# SubLowVoltagePS.net
KiCad netlist of a schematic drawn in Altium Designer
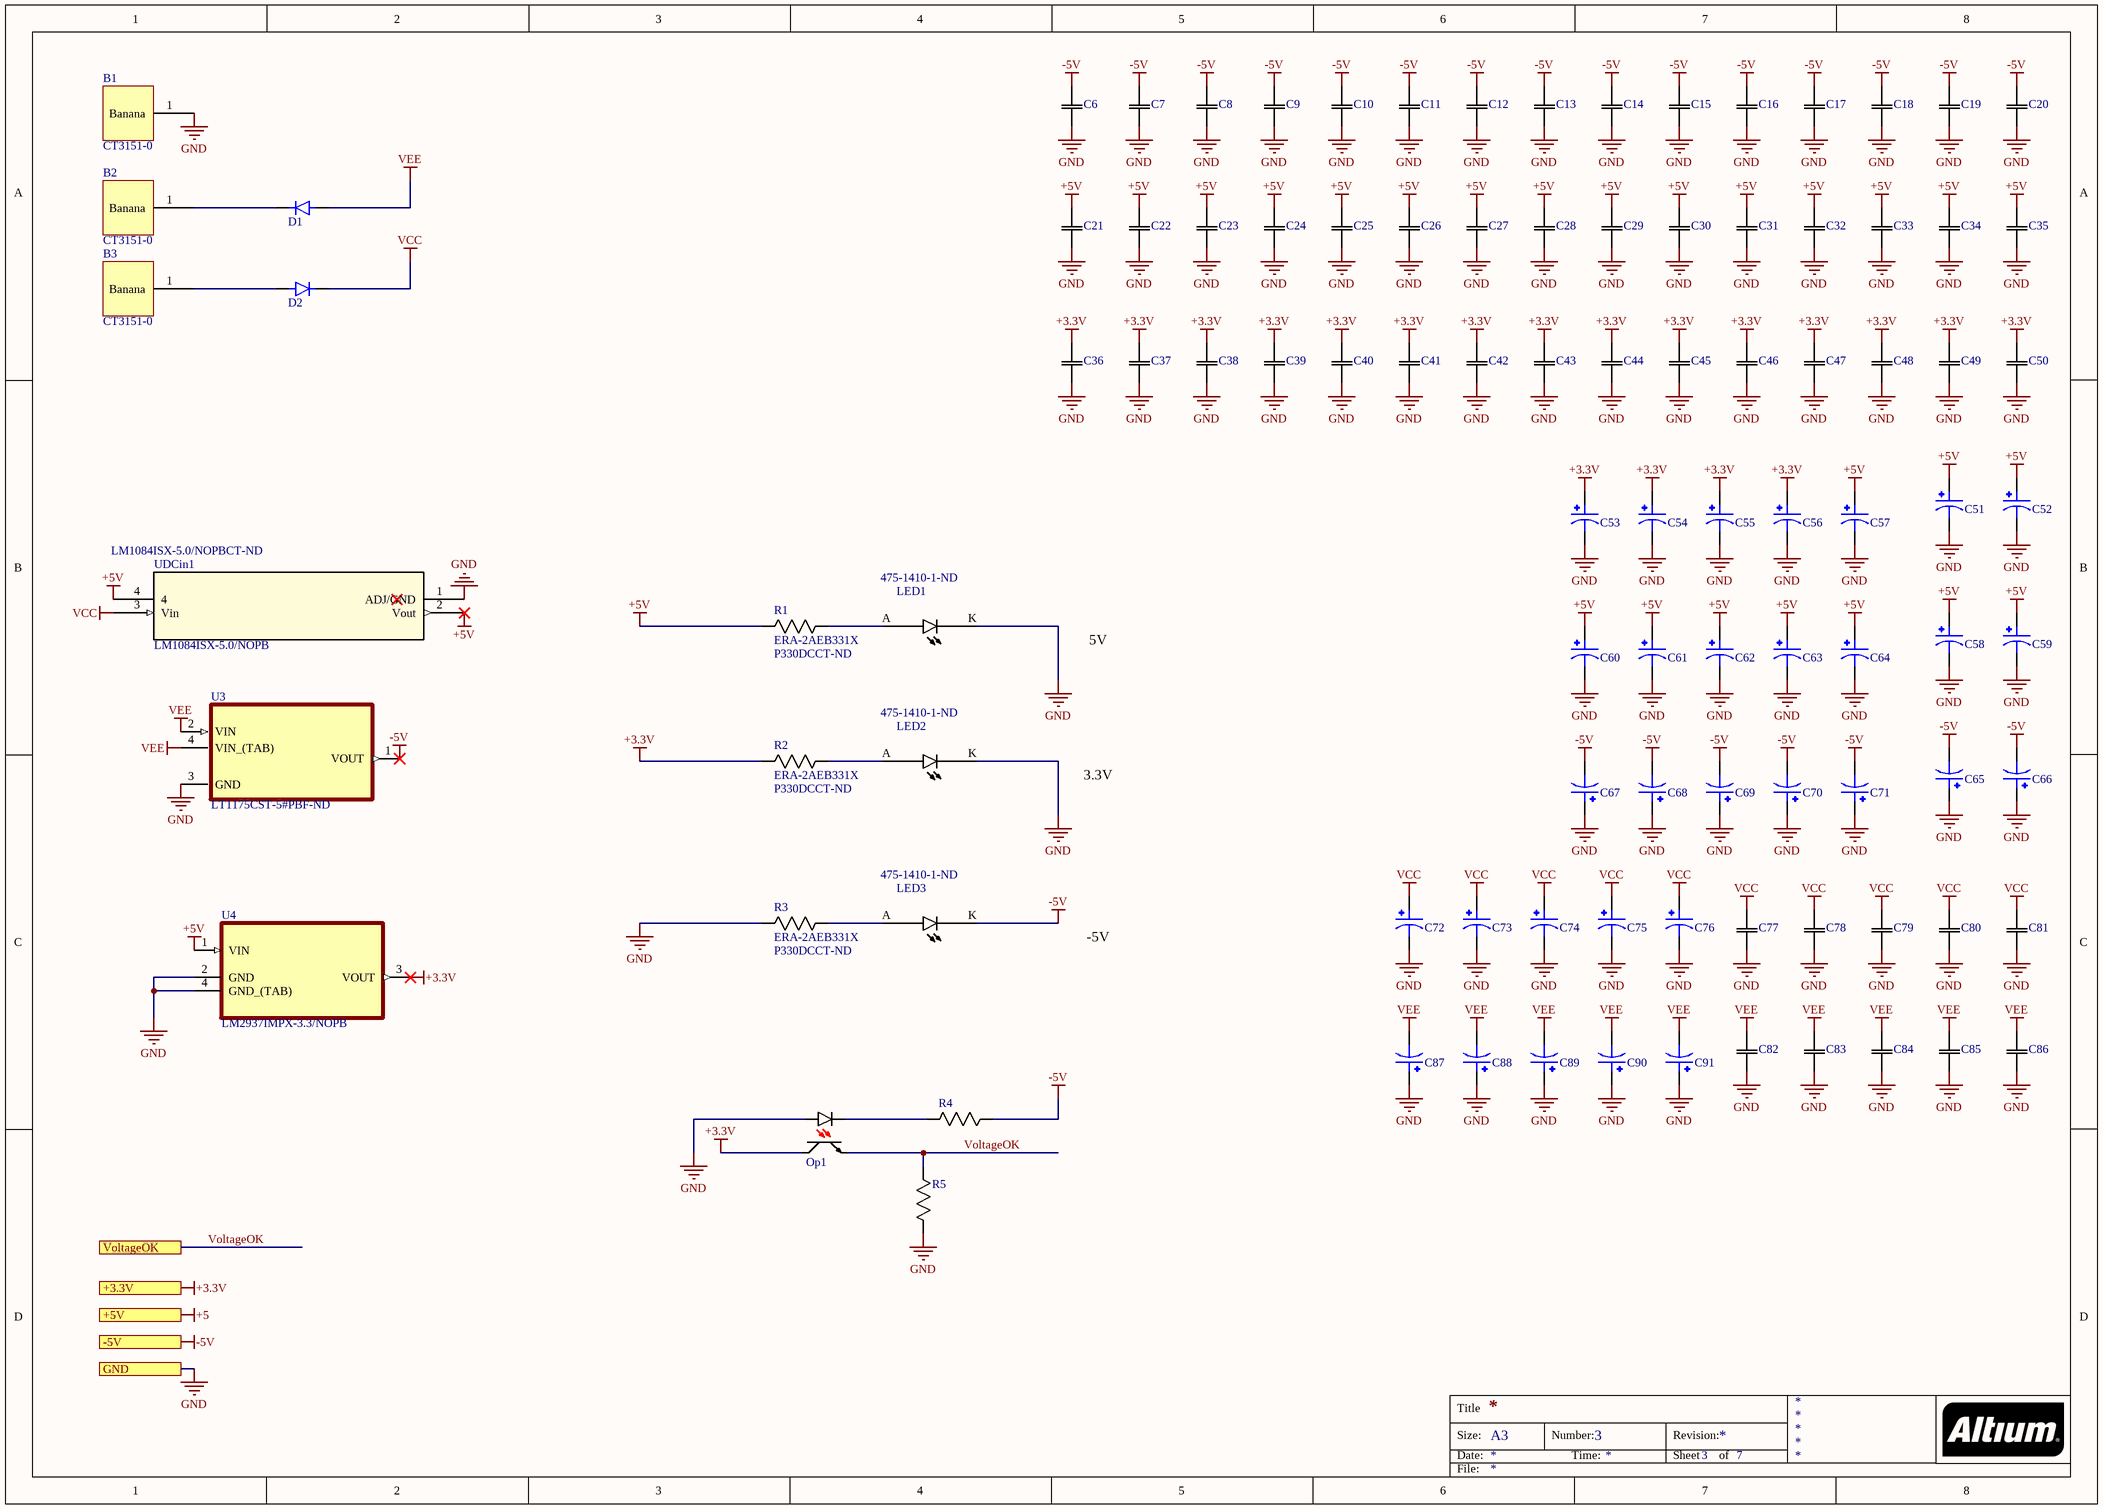
[diagram p0: SubLowVoltagePS.SchDoc]

(export (version "E")
  (design (tool "Eeschema 10.0.6"))
  (components
    (comp (ref "B1")
      (value "CT3151-0")
      (footprint "CT3151L")
      (libsource (lib "Afshin Library") (part "CT3151-0"))
    )
    (comp (ref "B2")
      (value "CT3151-0")
      (footprint "CT3151L")
      (libsource (lib "Afshin Library") (part "CT3151-0"))
    )
    (comp (ref "B3")
      (value "CT3151-0")
      (footprint "CT3151L")
      (libsource (lib "Afshin Library") (part "CT3151-0"))
    )
    (comp (ref "C6")
      (value "GRM155R71H102KA01J")
      (footprint "C0402")
      (libsource (lib "Afshin Library") (part "Cap_0402"))
    )
    (comp (ref "C7")
      (value "GRM155R71H102KA01J")
      (footprint "C0402")
      (libsource (lib "Afshin Library") (part "Cap_0402"))
    )
    (comp (ref "C8")
      (value "GRM155R71H102KA01J")
      (footprint "C0402")
      (libsource (lib "Afshin Library") (part "Cap_0402"))
    )
    (comp (ref "C9")
      (value "GRM155R71H102KA01J")
      (footprint "C0402")
      (libsource (lib "Afshin Library") (part "Cap_0402"))
    )
    (comp (ref "C10")
      (value "GRM155R71H102KA01J")
      (footprint "C0402")
      (libsource (lib "Afshin Library") (part "Cap_0402"))
    )
    (comp (ref "C11")
      (value "GRM155R71C103MA01D")
      (footprint "C0402")
      (libsource (lib "Afshin Library") (part "Cap_0402"))
    )
    (comp (ref "C12")
      (value "GRM155R71C103MA01D")
      (footprint "C0402")
      (libsource (lib "Afshin Library") (part "Cap_0402"))
    )
    (comp (ref "C13")
      (value "GRM155R71C103MA01D")
      (footprint "C0402")
      (libsource (lib "Afshin Library") (part "Cap_0402"))
    )
    (comp (ref "C14")
      (value "GRM155R71C103MA01D")
      (footprint "C0402")
      (libsource (lib "Afshin Library") (part "Cap_0402"))
    )
    (comp (ref "C15")
      (value "GRM155R71C103MA01D")
      (footprint "C0402")
      (libsource (lib "Afshin Library") (part "Cap_0402"))
    )
    (comp (ref "C16")
      (value "C0805C104Z5VACTU")
      (footprint "C0805")
      (libsource (lib "Afshin Library") (part "Cap_0805"))
    )
    (comp (ref "C17")
      (value "C0805C104Z5VACTU")
      (footprint "C0805")
      (libsource (lib "Afshin Library") (part "Cap_0805"))
    )
    (comp (ref "C18")
      (value "C0805C104Z5VACTU")
      (footprint "C0805")
      (libsource (lib "Afshin Library") (part "Cap_0805"))
    )
    (comp (ref "C19")
      (value "C0805C104Z5VACTU")
      (footprint "C0805")
      (libsource (lib "Afshin Library") (part "Cap_0805"))
    )
    (comp (ref "C20")
      (value "C0805C104Z5VACTU")
      (footprint "C0805")
      (libsource (lib "Afshin Library") (part "Cap_0805"))
    )
    (comp (ref "C21")
      (value "GRM155R71H102KA01J")
      (footprint "C0402")
      (libsource (lib "Afshin Library") (part "Cap_0402"))
    )
    (comp (ref "C22")
      (value "GRM155R71H102KA01J")
      (footprint "C0402")
      (libsource (lib "Afshin Library") (part "Cap_0402"))
    )
    (comp (ref "C23")
      (value "GRM155R71H102KA01J")
      (footprint "C0402")
      (libsource (lib "Afshin Library") (part "Cap_0402"))
    )
    (comp (ref "C24")
      (value "GRM155R71H102KA01J")
      (footprint "C0402")
      (libsource (lib "Afshin Library") (part "Cap_0402"))
    )
    (comp (ref "C25")
      (value "GRM155R71H102KA01J")
      (footprint "C0402")
      (libsource (lib "Afshin Library") (part "Cap_0402"))
    )
    (comp (ref "C26")
      (value "GRM155R71C103MA01D")
      (footprint "C0402")
      (libsource (lib "Afshin Library") (part "Cap_0402"))
    )
    (comp (ref "C27")
      (value "GRM155R71C103MA01D")
      (footprint "C0402")
      (libsource (lib "Afshin Library") (part "Cap_0402"))
    )
    (comp (ref "C28")
      (value "GRM155R71C103MA01D")
      (footprint "C0402")
      (libsource (lib "Afshin Library") (part "Cap_0402"))
    )
    (comp (ref "C29")
      (value "GRM155R71C103MA01D")
      (footprint "C0402")
      (libsource (lib "Afshin Library") (part "Cap_0402"))
    )
    (comp (ref "C30")
      (value "GRM155R71C103MA01D")
      (footprint "C0402")
      (libsource (lib "Afshin Library") (part "Cap_0402"))
    )
    (comp (ref "C31")
      (value "C0805C104Z5VACTU")
      (footprint "C0805")
      (libsource (lib "Afshin Library") (part "Cap_0805"))
    )
    (comp (ref "C32")
      (value "C0805C104Z5VACTU")
      (footprint "C0805")
      (libsource (lib "Afshin Library") (part "Cap_0805"))
    )
    (comp (ref "C33")
      (value "C0805C104Z5VACTU")
      (footprint "C0805")
      (libsource (lib "Afshin Library") (part "Cap_0805"))
    )
    (comp (ref "C34")
      (value "C0805C104Z5VACTU")
      (footprint "C0805")
      (libsource (lib "Afshin Library") (part "Cap_0805"))
    )
    (comp (ref "C35")
      (value "C0805C104Z5VACTU")
      (footprint "C0805")
      (libsource (lib "Afshin Library") (part "Cap_0805"))
    )
    (comp (ref "C36")
      (value "GRM155R71H102KA01J")
      (footprint "C0402")
      (libsource (lib "Afshin Library") (part "Cap_0402"))
    )
    (comp (ref "C37")
      (value "GRM155R71H102KA01J")
      (footprint "C0402")
      (libsource (lib "Afshin Library") (part "Cap_0402"))
    )
    (comp (ref "C38")
      (value "GRM155R71H102KA01J")
      (footprint "C0402")
      (libsource (lib "Afshin Library") (part "Cap_0402"))
    )
    (comp (ref "C39")
      (value "GRM155R71H102KA01J")
      (footprint "C0402")
      (libsource (lib "Afshin Library") (part "Cap_0402"))
    )
    (comp (ref "C40")
      (value "GRM155R71H102KA01J")
      (footprint "C0402")
      (libsource (lib "Afshin Library") (part "Cap_0402"))
    )
    (comp (ref "C41")
      (value "GRM155R71C103MA01D")
      (footprint "C0402")
      (libsource (lib "Afshin Library") (part "Cap_0402"))
    )
    (comp (ref "C42")
      (value "GRM155R71C103MA01D")
      (footprint "C0402")
      (libsource (lib "Afshin Library") (part "Cap_0402"))
    )
    (comp (ref "C43")
      (value "GRM155R71C103MA01D")
      (footprint "C0402")
      (libsource (lib "Afshin Library") (part "Cap_0402"))
    )
    (comp (ref "C44")
      (value "GRM155R71C103MA01D")
      (footprint "C0402")
      (libsource (lib "Afshin Library") (part "Cap_0402"))
    )
    (comp (ref "C45")
      (value "GRM155R71C103MA01D")
      (footprint "C0402")
      (libsource (lib "Afshin Library") (part "Cap_0402"))
    )
    (comp (ref "C46")
      (value "C0805C104Z5VACTU")
      (footprint "C0805")
      (libsource (lib "Afshin Library") (part "Cap_0805"))
    )
    (comp (ref "C47")
      (value "C0805C104Z5VACTU")
      (footprint "C0805")
      (libsource (lib "Afshin Library") (part "Cap_0805"))
    )
    (comp (ref "C48")
      (value "C0805C104Z5VACTU")
      (footprint "C0805")
      (libsource (lib "Afshin Library") (part "Cap_0805"))
    )
    (comp (ref "C49")
      (value "C0805C104Z5VACTU")
      (footprint "C0805")
      (libsource (lib "Afshin Library") (part "Cap_0805"))
    )
    (comp (ref "C50")
      (value "C0805C104Z5VACTU")
      (footprint "C0805")
      (libsource (lib "Afshin Library") (part "Cap_0805"))
    )
    (comp (ref "C51")
      (value "T55A107M6R3C0200")
      (footprint "C1206")
      (description "Tantalium")
      (libsource (lib "") (part "Cap_1206_1"))
    )
    (comp (ref "C52")
      (value "T55A107M6R3C0200")
      (footprint "C1206")
      (description "Tantalium")
      (libsource (lib "") (part "Cap_1206_1"))
    )
    (comp (ref "C53")
      (value "T491A104K050AT")
      (footprint "C1206")
      (description "Tantalium")
      (libsource (lib "") (part "Cap_1206_1"))
    )
    (comp (ref "C54")
      (value "T491A104K050AT")
      (footprint "C1206")
      (description "Tantalium")
      (libsource (lib "") (part "Cap_1206_1"))
    )
    (comp (ref "C55")
      (value "T491A104K050AT")
      (footprint "C1206")
      (description "Tantalium")
      (libsource (lib "") (part "Cap_1206_1"))
    )
    (comp (ref "C56")
      (value "T491A104K050AT")
      (footprint "C1206")
      (description "Tantalium")
      (libsource (lib "") (part "Cap_1206_1"))
    )
    (comp (ref "C57")
      (value "T491A104K050AT")
      (footprint "C1206")
      (description "Tantalium")
      (libsource (lib "") (part "Cap_1206_1"))
    )
    (comp (ref "C58")
      (value "T55A107M6R3C0200")
      (footprint "C1206")
      (description "Tantalium")
      (libsource (lib "") (part "Cap_1206_1"))
    )
    (comp (ref "C59")
      (value "T55A107M6R3C0200")
      (footprint "C1206")
      (description "Tantalium")
      (libsource (lib "") (part "Cap_1206_1"))
    )
    (comp (ref "C60")
      (value "T491A104K050AT")
      (footprint "C1206")
      (description "Tantalium")
      (libsource (lib "") (part "Cap_1206_1"))
    )
    (comp (ref "C61")
      (value "T491A104K050AT")
      (footprint "C1206")
      (description "Tantalium")
      (libsource (lib "") (part "Cap_1206_1"))
    )
    (comp (ref "C62")
      (value "T491A104K050AT")
      (footprint "C1206")
      (description "Tantalium")
      (libsource (lib "") (part "Cap_1206_1"))
    )
    (comp (ref "C63")
      (value "T491A104K050AT")
      (footprint "C1206")
      (description "Tantalium")
      (libsource (lib "") (part "Cap_1206_1"))
    )
    (comp (ref "C64")
      (value "T491A104K050AT")
      (footprint "C1206")
      (description "Tantalium")
      (libsource (lib "") (part "Cap_1206_1"))
    )
    (comp (ref "C65")
      (value "T55A107M6R3C0200")
      (footprint "C1206")
      (description "Tantalium")
      (libsource (lib "Afshin Library") (part "Cap_1206"))
    )
    (comp (ref "C66")
      (value "T55A107M6R3C0200")
      (footprint "C1206")
      (description "Tantalium")
      (libsource (lib "Afshin Library") (part "Cap_1206"))
    )
    (comp (ref "C67")
      (value "T491A104K050AT")
      (footprint "C1206")
      (description "Tantalium")
      (libsource (lib "Afshin Library") (part "Cap_1206"))
    )
    (comp (ref "C68")
      (value "T491A104K050AT")
      (footprint "C1206")
      (description "Tantalium")
      (libsource (lib "Afshin Library") (part "Cap_1206"))
    )
    (comp (ref "C69")
      (value "T491A104K050AT")
      (footprint "C1206")
      (description "Tantalium")
      (libsource (lib "Afshin Library") (part "Cap_1206"))
    )
    (comp (ref "C70")
      (value "T491A104K050AT")
      (footprint "C1206")
      (description "Tantalium")
      (libsource (lib "Afshin Library") (part "Cap_1206"))
    )
    (comp (ref "C71")
      (value "T491A104K050AT")
      (footprint "C1206")
      (description "Tantalium")
      (libsource (lib "Afshin Library") (part "Cap_1206"))
    )
    (comp (ref "C72")
      (value "F931D106MAA")
      (footprint "C1206")
      (description "Tantalium")
      (libsource (lib "") (part "Cap_1206_1"))
    )
    (comp (ref "C73")
      (value "F931D106MAA")
      (footprint "C1206")
      (description "Tantalium")
      (libsource (lib "") (part "Cap_1206_1"))
    )
    (comp (ref "C74")
      (value "F931D106MAA")
      (footprint "C1206")
      (description "Tantalium")
      (libsource (lib "") (part "Cap_1206_1"))
    )
    (comp (ref "C75")
      (value "F931D106MAA")
      (footprint "C1206")
      (description "Tantalium")
      (libsource (lib "") (part "Cap_1206_1"))
    )
    (comp (ref "C76")
      (value "F931D106MAA")
      (footprint "C1206")
      (description "Tantalium")
      (libsource (lib "") (part "Cap_1206_1"))
    )
    (comp (ref "C77")
      (value "GRM155R71C103MA01D")
      (footprint "C0402")
      (libsource (lib "Afshin Library") (part "Cap_0402"))
    )
    (comp (ref "C78")
      (value "GRM155R71C103MA01D")
      (footprint "C0402")
      (libsource (lib "Afshin Library") (part "Cap_0402"))
    )
    (comp (ref "C79")
      (value "GRM155R71C103MA01D")
      (footprint "C0402")
      (libsource (lib "Afshin Library") (part "Cap_0402"))
    )
    (comp (ref "C80")
      (value "GRM155R71C103MA01D")
      (footprint "C0402")
      (libsource (lib "Afshin Library") (part "Cap_0402"))
    )
    (comp (ref "C81")
      (value "GRM155R71C103MA01D")
      (footprint "C0402")
      (libsource (lib "Afshin Library") (part "Cap_0402"))
    )
    (comp (ref "C82")
      (value "GRM155R71C103MA01D")
      (footprint "C0402")
      (libsource (lib "Afshin Library") (part "Cap_0402"))
    )
    (comp (ref "C83")
      (value "GRM155R71C103MA01D")
      (footprint "C0402")
      (libsource (lib "Afshin Library") (part "Cap_0402"))
    )
    (comp (ref "C84")
      (value "GRM155R71C103MA01D")
      (footprint "C0402")
      (libsource (lib "Afshin Library") (part "Cap_0402"))
    )
    (comp (ref "C85")
      (value "GRM155R71C103MA01D")
      (footprint "C0402")
      (libsource (lib "Afshin Library") (part "Cap_0402"))
    )
    (comp (ref "C86")
      (value "GRM155R71C103MA01D")
      (footprint "C0402")
      (libsource (lib "Afshin Library") (part "Cap_0402"))
    )
    (comp (ref "C87")
      (value "F931D106MAA")
      (footprint "C1206")
      (description "Tantalium")
      (libsource (lib "Afshin Library") (part "Cap_1206"))
    )
    (comp (ref "C88")
      (value "F931D106MAA")
      (footprint "C1206")
      (description "Tantalium")
      (libsource (lib "Afshin Library") (part "Cap_1206"))
    )
    (comp (ref "C89")
      (value "F931D106MAA")
      (footprint "C1206")
      (description "Tantalium")
      (libsource (lib "Afshin Library") (part "Cap_1206"))
    )
    (comp (ref "C90")
      (value "F931D106MAA")
      (footprint "C1206")
      (description "Tantalium")
      (libsource (lib "Afshin Library") (part "Cap_1206"))
    )
    (comp (ref "C91")
      (value "F931D106MAA")
      (footprint "C1206")
      (description "Tantalium")
      (libsource (lib "Afshin Library") (part "Cap_1206"))
    )
    (comp (ref "D1")
      (value "CD1408-R11000")
      (footprint "CD1408")
      (description "Diode Standard 1000V 1A Surface Mount 1408")
      (libsource (lib "Afshin Library") (part "CD1408-R11000"))
    )
    (comp (ref "D2")
      (value "CD1408-R11000")
      (footprint "CD1408")
      (description "Diode Standard 1000V 1A Surface Mount 1408")
      (libsource (lib "Afshin Library") (part "CD1408-R11000"))
    )
    (comp (ref "LED1")
      (value "LG R971-KN-1")
      (footprint "LEDG0805")
      (description "LED:\r\nLH R974-LP-1\r\nLG R971-KN-1\r\nLY R976-PS-36")
      (fields (field (name "SUPPLIER PART NUMBER 1") "475-1410-1-ND"))
      (libsource (lib "Afshin Library") (part "LED_0805"))
    )
    (comp (ref "LED2")
      (value "LG R971-KN-1")
      (footprint "LEDG0805")
      (description "LED:\r\nLH R974-LP-1\r\nLG R971-KN-1\r\nLY R976-PS-36")
      (fields (field (name "SUPPLIER PART NUMBER 1") "475-1410-1-ND"))
      (libsource (lib "Afshin Library") (part "LED_0805"))
    )
    (comp (ref "LED3")
      (value "LG R971-KN-1")
      (footprint "LEDG0805")
      (description "LED:\r\nLH R974-LP-1\r\nLG R971-KN-1\r\nLY R976-PS-36")
      (fields (field (name "SUPPLIER PART NUMBER 1") "475-1410-1-ND"))
      (libsource (lib "Afshin Library") (part "LED_0805"))
    )
    (comp (ref "Op1")
      (value "TLP291(GB,SE")
      (footprint "4-SOIC")
      (libsource (lib "Afshin Library") (part "TLP291"))
    )
    (comp (ref "R1")
      (value "ERA-2AEB331X")
      (footprint "0402")
      (fields (field (name "SUPPLIER PART NUMBER 1") "P330DCCT-ND"))
      (libsource (lib "Afshin Library") (part "Res_0805"))
    )
    (comp (ref "R2")
      (value "ERA-2AEB331X")
      (footprint "0402")
      (fields (field (name "SUPPLIER PART NUMBER 1") "P330DCCT-ND"))
      (libsource (lib "Afshin Library") (part "Res_0805"))
    )
    (comp (ref "R3")
      (value "ERA-2AEB331X")
      (footprint "0402")
      (fields (field (name "SUPPLIER PART NUMBER 1") "P330DCCT-ND"))
      (libsource (lib "Afshin Library") (part "Res_0805"))
    )
    (comp (ref "R4")
      (value "ERA-2AEB331X")
      (footprint "0402")
      (libsource (lib "Afshin Library") (part "Res_0805"))
    )
    (comp (ref "R5")
      (value "RK73B1ETTP103J")
      (footprint "R0402")
      (libsource (lib "Afshin Library") (part "Res_0402"))
    )
    (comp (ref "U3")
      (value "LT1175CST-5#PBF")
      (footprint "SOT230P700X180-4N")
      (description "IC REG LINEAR -5V 500MA SOT223-3")
      (fields
        (field (name "MP") "LM2937IMPX-3.3/NOPB")
        (field (name "MF") "Texas Instruments")
        (field (name "SUPPLIER PART NUMBER 1") "LT1175CST-5#PBF-ND")
      )
      (libsource (lib "Afshin Library") (part "LT1175CST-5#PBF"))
    )
    (comp (ref "U4")
      (value "LM2937IMPX-3.3/NOPB")
      (footprint "SOT230P700X180-4N")
      (description "Linear Voltage Regulator IC 1 Output 400mA SOT-223-4")
      (fields (field (name "MF") "Texas Instruments"))
      (libsource (lib "Afshin Library") (part "LM2937IMPX-3.3/NOPB"))
    )
    (comp (ref "UDCin1")
      (value "LM1084ISX-5.0/NOPB")
      (footprint "TS3B")
      (description "No Description Available")
      (fields
        (field (name "SUPPLIER PART NUMBER 1") "LM1084ISX-5.0/NOPBCT-ND")
        (field (name "COPYRIGHT") "Copyright (C) 2018 Accelerated Designs. All rights reserved")
      )
      (libsource (lib "Afshin Library") (part "LM1084ISX-5.0/NO"))
    )
  )
  (nets
    (net (code "1") (name "+3.3V") (class "Default")
      (node (ref "C36") (pin "2") (pinfunction "2_2") (pintype "passive"))
      (node (ref "C37") (pin "2") (pinfunction "2_2") (pintype "passive"))
      (node (ref "C38") (pin "2") (pinfunction "2_2") (pintype "passive"))
      (node (ref "C39") (pin "2") (pinfunction "2_2") (pintype "passive"))
      (node (ref "C40") (pin "2") (pinfunction "2_2") (pintype "passive"))
      (node (ref "C41") (pin "2") (pinfunction "2_2") (pintype "passive"))
      (node (ref "C42") (pin "2") (pinfunction "2_2") (pintype "passive"))
      (node (ref "C43") (pin "2") (pinfunction "2_2") (pintype "passive"))
      (node (ref "C44") (pin "2") (pinfunction "2_2") (pintype "passive"))
      (node (ref "C45") (pin "2") (pinfunction "2_2") (pintype "passive"))
      (node (ref "C46") (pin "2") (pinfunction "2_2") (pintype "passive"))
      (node (ref "C47") (pin "2") (pinfunction "2_2") (pintype "passive"))
      (node (ref "C48") (pin "2") (pinfunction "2_2") (pintype "passive"))
      (node (ref "C49") (pin "2") (pinfunction "2_2") (pintype "passive"))
      (node (ref "C50") (pin "2") (pinfunction "2_2") (pintype "passive"))
      (node (ref "C53") (pin "1") (pinfunction "POS_1") (pintype "passive"))
      (node (ref "C54") (pin "1") (pinfunction "POS_1") (pintype "passive"))
      (node (ref "C55") (pin "1") (pinfunction "POS_1") (pintype "passive"))
      (node (ref "C56") (pin "1") (pinfunction "POS_1") (pintype "passive"))
      (node (ref "Op1") (pin "4") (pinfunction "4_4") (pintype "passive"))
      (node (ref "R2") (pin "2") (pinfunction "2_2") (pintype "passive"))
      (node (ref "U4") (pin "3") (pinfunction "VOUT_3") (pintype "output"))
    )
    (net (code "2") (name "+5") (class "Default")
      (node (ref "C21") (pin "2") (pinfunction "2_2") (pintype "passive"))
      (node (ref "C22") (pin "2") (pinfunction "2_2") (pintype "passive"))
      (node (ref "C23") (pin "2") (pinfunction "2_2") (pintype "passive"))
      (node (ref "C24") (pin "2") (pinfunction "2_2") (pintype "passive"))
      (node (ref "C25") (pin "2") (pinfunction "2_2") (pintype "passive"))
      (node (ref "C26") (pin "2") (pinfunction "2_2") (pintype "passive"))
      (node (ref "C27") (pin "2") (pinfunction "2_2") (pintype "passive"))
      (node (ref "C28") (pin "2") (pinfunction "2_2") (pintype "passive"))
      (node (ref "C29") (pin "2") (pinfunction "2_2") (pintype "passive"))
      (node (ref "C30") (pin "2") (pinfunction "2_2") (pintype "passive"))
      (node (ref "C31") (pin "2") (pinfunction "2_2") (pintype "passive"))
      (node (ref "C32") (pin "2") (pinfunction "2_2") (pintype "passive"))
      (node (ref "C33") (pin "2") (pinfunction "2_2") (pintype "passive"))
      (node (ref "C34") (pin "2") (pinfunction "2_2") (pintype "passive"))
      (node (ref "C35") (pin "2") (pinfunction "2_2") (pintype "passive"))
      (node (ref "C51") (pin "1") (pinfunction "POS_1") (pintype "passive"))
      (node (ref "C52") (pin "1") (pinfunction "POS_1") (pintype "passive"))
      (node (ref "C57") (pin "1") (pinfunction "POS_1") (pintype "passive"))
      (node (ref "C58") (pin "1") (pinfunction "POS_1") (pintype "passive"))
      (node (ref "C59") (pin "1") (pinfunction "POS_1") (pintype "passive"))
      (node (ref "C60") (pin "1") (pinfunction "POS_1") (pintype "passive"))
      (node (ref "C61") (pin "1") (pinfunction "POS_1") (pintype "passive"))
      (node (ref "C62") (pin "1") (pinfunction "POS_1") (pintype "passive"))
      (node (ref "C63") (pin "1") (pinfunction "POS_1") (pintype "passive"))
      (node (ref "C64") (pin "1") (pinfunction "POS_1") (pintype "passive"))
      (node (ref "R1") (pin "2") (pinfunction "2_2") (pintype "passive"))
      (node (ref "U4") (pin "1") (pinfunction "VIN_1") (pintype "input"))
      (node (ref "UDCin1") (pin "2") (pinfunction "Vout_2") (pintype "output"))
      (node (ref "UDCin1") (pin "4") (pinfunction "4_4") (pintype "passive"))
    )
    (net (code "3") (name "-5V") (class "Default")
      (node (ref "C10") (pin "2") (pinfunction "2_2") (pintype "passive"))
      (node (ref "C11") (pin "2") (pinfunction "2_2") (pintype "passive"))
      (node (ref "C12") (pin "2") (pinfunction "2_2") (pintype "passive"))
      (node (ref "C13") (pin "2") (pinfunction "2_2") (pintype "passive"))
      (node (ref "C14") (pin "2") (pinfunction "2_2") (pintype "passive"))
      (node (ref "C15") (pin "2") (pinfunction "2_2") (pintype "passive"))
      (node (ref "C16") (pin "2") (pinfunction "2_2") (pintype "passive"))
      (node (ref "C17") (pin "2") (pinfunction "2_2") (pintype "passive"))
      (node (ref "C18") (pin "2") (pinfunction "2_2") (pintype "passive"))
      (node (ref "C19") (pin "2") (pinfunction "2_2") (pintype "passive"))
      (node (ref "C20") (pin "2") (pinfunction "2_2") (pintype "passive"))
      (node (ref "C6") (pin "2") (pinfunction "2_2") (pintype "passive"))
      (node (ref "C65") (pin "2") (pinfunction "NEG_2") (pintype "passive"))
      (node (ref "C66") (pin "2") (pinfunction "NEG_2") (pintype "passive"))
      (node (ref "C67") (pin "2") (pinfunction "NEG_2") (pintype "passive"))
      (node (ref "C68") (pin "2") (pinfunction "NEG_2") (pintype "passive"))
      (node (ref "C69") (pin "2") (pinfunction "NEG_2") (pintype "passive"))
      (node (ref "C7") (pin "2") (pinfunction "2_2") (pintype "passive"))
      (node (ref "C70") (pin "2") (pinfunction "NEG_2") (pintype "passive"))
      (node (ref "C71") (pin "2") (pinfunction "NEG_2") (pintype "passive"))
      (node (ref "C8") (pin "2") (pinfunction "2_2") (pintype "passive"))
      (node (ref "C9") (pin "2") (pinfunction "2_2") (pintype "passive"))
      (node (ref "LED3") (pin "K") (pinfunction "k_K") (pintype "passive"))
      (node (ref "R4") (pin "1") (pinfunction "1_1") (pintype "passive"))
      (node (ref "U3") (pin "1") (pinfunction "VOUT_1") (pintype "output"))
    )
    (net (code "4") (name "/VoltageOK") (class "Default")
      (node (ref "Op1") (pin "3") (pinfunction "3_3") (pintype "passive"))
      (node (ref "R5") (pin "2") (pinfunction "2_2") (pintype "passive"))
    )
    (net (code "5") (name "GND") (class "Default")
      (node (ref "B1") (pin "1") (pinfunction "Banana_1") (pintype "passive"))
      (node (ref "C10") (pin "1") (pinfunction "1_1") (pintype "passive"))
      (node (ref "C11") (pin "1") (pinfunction "1_1") (pintype "passive"))
      (node (ref "C12") (pin "1") (pinfunction "1_1") (pintype "passive"))
      (node (ref "C13") (pin "1") (pinfunction "1_1") (pintype "passive"))
      (node (ref "C14") (pin "1") (pinfunction "1_1") (pintype "passive"))
      (node (ref "C15") (pin "1") (pinfunction "1_1") (pintype "passive"))
      (node (ref "C16") (pin "1") (pinfunction "1_1") (pintype "passive"))
      (node (ref "C17") (pin "1") (pinfunction "1_1") (pintype "passive"))
      (node (ref "C18") (pin "1") (pinfunction "1_1") (pintype "passive"))
      (node (ref "C19") (pin "1") (pinfunction "1_1") (pintype "passive"))
      (node (ref "C20") (pin "1") (pinfunction "1_1") (pintype "passive"))
      (node (ref "C21") (pin "1") (pinfunction "1_1") (pintype "passive"))
      (node (ref "C22") (pin "1") (pinfunction "1_1") (pintype "passive"))
      (node (ref "C23") (pin "1") (pinfunction "1_1") (pintype "passive"))
      (node (ref "C24") (pin "1") (pinfunction "1_1") (pintype "passive"))
      (node (ref "C25") (pin "1") (pinfunction "1_1") (pintype "passive"))
      (node (ref "C26") (pin "1") (pinfunction "1_1") (pintype "passive"))
      (node (ref "C27") (pin "1") (pinfunction "1_1") (pintype "passive"))
      (node (ref "C28") (pin "1") (pinfunction "1_1") (pintype "passive"))
      (node (ref "C29") (pin "1") (pinfunction "1_1") (pintype "passive"))
      (node (ref "C30") (pin "1") (pinfunction "1_1") (pintype "passive"))
      (node (ref "C31") (pin "1") (pinfunction "1_1") (pintype "passive"))
      (node (ref "C32") (pin "1") (pinfunction "1_1") (pintype "passive"))
      (node (ref "C33") (pin "1") (pinfunction "1_1") (pintype "passive"))
      (node (ref "C34") (pin "1") (pinfunction "1_1") (pintype "passive"))
      (node (ref "C35") (pin "1") (pinfunction "1_1") (pintype "passive"))
      (node (ref "C36") (pin "1") (pinfunction "1_1") (pintype "passive"))
      (node (ref "C37") (pin "1") (pinfunction "1_1") (pintype "passive"))
      (node (ref "C38") (pin "1") (pinfunction "1_1") (pintype "passive"))
      (node (ref "C39") (pin "1") (pinfunction "1_1") (pintype "passive"))
      (node (ref "C40") (pin "1") (pinfunction "1_1") (pintype "passive"))
      (node (ref "C41") (pin "1") (pinfunction "1_1") (pintype "passive"))
      (node (ref "C42") (pin "1") (pinfunction "1_1") (pintype "passive"))
      (node (ref "C43") (pin "1") (pinfunction "1_1") (pintype "passive"))
      (node (ref "C44") (pin "1") (pinfunction "1_1") (pintype "passive"))
      (node (ref "C45") (pin "1") (pinfunction "1_1") (pintype "passive"))
      (node (ref "C46") (pin "1") (pinfunction "1_1") (pintype "passive"))
      (node (ref "C47") (pin "1") (pinfunction "1_1") (pintype "passive"))
      (node (ref "C48") (pin "1") (pinfunction "1_1") (pintype "passive"))
      (node (ref "C49") (pin "1") (pinfunction "1_1") (pintype "passive"))
      (node (ref "C50") (pin "1") (pinfunction "1_1") (pintype "passive"))
      (node (ref "C51") (pin "2") (pinfunction "NEG_2") (pintype "passive"))
      (node (ref "C52") (pin "2") (pinfunction "NEG_2") (pintype "passive"))
      (node (ref "C53") (pin "2") (pinfunction "NEG_2") (pintype "passive"))
      (node (ref "C54") (pin "2") (pinfunction "NEG_2") (pintype "passive"))
      (node (ref "C55") (pin "2") (pinfunction "NEG_2") (pintype "passive"))
      (node (ref "C56") (pin "2") (pinfunction "NEG_2") (pintype "passive"))
      (node (ref "C57") (pin "2") (pinfunction "NEG_2") (pintype "passive"))
      (node (ref "C58") (pin "2") (pinfunction "NEG_2") (pintype "passive"))
      (node (ref "C59") (pin "2") (pinfunction "NEG_2") (pintype "passive"))
      (node (ref "C6") (pin "1") (pinfunction "1_1") (pintype "passive"))
      (node (ref "C60") (pin "2") (pinfunction "NEG_2") (pintype "passive"))
      (node (ref "C61") (pin "2") (pinfunction "NEG_2") (pintype "passive"))
      (node (ref "C62") (pin "2") (pinfunction "NEG_2") (pintype "passive"))
      (node (ref "C63") (pin "2") (pinfunction "NEG_2") (pintype "passive"))
      (node (ref "C64") (pin "2") (pinfunction "NEG_2") (pintype "passive"))
      (node (ref "C65") (pin "1") (pinfunction "POS_1") (pintype "passive"))
      (node (ref "C66") (pin "1") (pinfunction "POS_1") (pintype "passive"))
      (node (ref "C67") (pin "1") (pinfunction "POS_1") (pintype "passive"))
      (node (ref "C68") (pin "1") (pinfunction "POS_1") (pintype "passive"))
      (node (ref "C69") (pin "1") (pinfunction "POS_1") (pintype "passive"))
      (node (ref "C7") (pin "1") (pinfunction "1_1") (pintype "passive"))
      (node (ref "C70") (pin "1") (pinfunction "POS_1") (pintype "passive"))
      (node (ref "C71") (pin "1") (pinfunction "POS_1") (pintype "passive"))
      (node (ref "C72") (pin "2") (pinfunction "NEG_2") (pintype "passive"))
      (node (ref "C73") (pin "2") (pinfunction "NEG_2") (pintype "passive"))
      (node (ref "C74") (pin "2") (pinfunction "NEG_2") (pintype "passive"))
      (node (ref "C75") (pin "2") (pinfunction "NEG_2") (pintype "passive"))
      (node (ref "C76") (pin "2") (pinfunction "NEG_2") (pintype "passive"))
      (node (ref "C77") (pin "1") (pinfunction "1_1") (pintype "passive"))
      (node (ref "C78") (pin "1") (pinfunction "1_1") (pintype "passive"))
      (node (ref "C79") (pin "1") (pinfunction "1_1") (pintype "passive"))
      (node (ref "C8") (pin "1") (pinfunction "1_1") (pintype "passive"))
      (node (ref "C80") (pin "1") (pinfunction "1_1") (pintype "passive"))
      (node (ref "C81") (pin "1") (pinfunction "1_1") (pintype "passive"))
      (node (ref "C82") (pin "1") (pinfunction "1_1") (pintype "passive"))
      (node (ref "C83") (pin "1") (pinfunction "1_1") (pintype "passive"))
      (node (ref "C84") (pin "1") (pinfunction "1_1") (pintype "passive"))
      (node (ref "C85") (pin "1") (pinfunction "1_1") (pintype "passive"))
      (node (ref "C86") (pin "1") (pinfunction "1_1") (pintype "passive"))
      (node (ref "C87") (pin "1") (pinfunction "POS_1") (pintype "passive"))
      (node (ref "C88") (pin "1") (pinfunction "POS_1") (pintype "passive"))
      (node (ref "C89") (pin "1") (pinfunction "POS_1") (pintype "passive"))
      (node (ref "C9") (pin "1") (pinfunction "1_1") (pintype "passive"))
      (node (ref "C90") (pin "1") (pinfunction "POS_1") (pintype "passive"))
      (node (ref "C91") (pin "1") (pinfunction "POS_1") (pintype "passive"))
      (node (ref "LED1") (pin "K") (pinfunction "k_K") (pintype "passive"))
      (node (ref "LED2") (pin "K") (pinfunction "k_K") (pintype "passive"))
      (node (ref "Op1") (pin "1") (pinfunction "1_1") (pintype "passive"))
      (node (ref "R3") (pin "2") (pinfunction "2_2") (pintype "passive"))
      (node (ref "R5") (pin "1") (pinfunction "1_1") (pintype "passive"))
      (node (ref "U3") (pin "3") (pinfunction "GND_3") (pintype "passive"))
      (node (ref "U4") (pin "2") (pinfunction "GND_2") (pintype "passive"))
      (node (ref "U4") (pin "4") (pinfunction "GND_(TAB)_4") (pintype "passive"))
      (node (ref "UDCin1") (pin "1") (pinfunction "ADJ/GND_1") (pintype "passive"))
    )
    (net (code "6") (name "Net-(B2-Banana)") (class "Default")
      (node (ref "B2") (pin "1") (pinfunction "Banana_1") (pintype "passive"))
      (node (ref "D1") (pin "1") (pinfunction "1_1") (pintype "passive"))
    )
    (net (code "7") (name "Net-(B3-Banana)") (class "Default")
      (node (ref "B3") (pin "1") (pinfunction "Banana_1") (pintype "passive"))
      (node (ref "D2") (pin "2") (pinfunction "2_2") (pintype "passive"))
    )
    (net (code "8") (name "Net-(LED1-PadA)") (class "Default")
      (node (ref "LED1") (pin "A") (pinfunction "A_A") (pintype "passive"))
      (node (ref "R1") (pin "1") (pinfunction "1_1") (pintype "passive"))
    )
    (net (code "9") (name "Net-(LED2-PadA)") (class "Default")
      (node (ref "LED2") (pin "A") (pinfunction "A_A") (pintype "passive"))
      (node (ref "R2") (pin "1") (pinfunction "1_1") (pintype "passive"))
    )
    (net (code "10") (name "Net-(LED3-PadA)") (class "Default")
      (node (ref "LED3") (pin "A") (pinfunction "A_A") (pintype "passive"))
      (node (ref "R3") (pin "1") (pinfunction "1_1") (pintype "passive"))
    )
    (net (code "11") (name "Net-(Op1-Pad2)") (class "Default")
      (node (ref "Op1") (pin "2") (pinfunction "2_2") (pintype "passive"))
      (node (ref "R4") (pin "2") (pinfunction "2_2") (pintype "passive"))
    )
    (net (code "12") (name "VCC") (class "Default")
      (node (ref "C72") (pin "1") (pinfunction "POS_1") (pintype "passive"))
      (node (ref "C73") (pin "1") (pinfunction "POS_1") (pintype "passive"))
      (node (ref "C74") (pin "1") (pinfunction "POS_1") (pintype "passive"))
      (node (ref "C75") (pin "1") (pinfunction "POS_1") (pintype "passive"))
      (node (ref "C76") (pin "1") (pinfunction "POS_1") (pintype "passive"))
      (node (ref "C77") (pin "2") (pinfunction "2_2") (pintype "passive"))
      (node (ref "C78") (pin "2") (pinfunction "2_2") (pintype "passive"))
      (node (ref "C79") (pin "2") (pinfunction "2_2") (pintype "passive"))
      (node (ref "C80") (pin "2") (pinfunction "2_2") (pintype "passive"))
      (node (ref "C81") (pin "2") (pinfunction "2_2") (pintype "passive"))
      (node (ref "D2") (pin "1") (pinfunction "1_1") (pintype "passive"))
      (node (ref "UDCin1") (pin "3") (pinfunction "Vin_3") (pintype "input"))
    )
    (net (code "13") (name "VEE") (class "Default")
      (node (ref "C82") (pin "2") (pinfunction "2_2") (pintype "passive"))
      (node (ref "C83") (pin "2") (pinfunction "2_2") (pintype "passive"))
      (node (ref "C84") (pin "2") (pinfunction "2_2") (pintype "passive"))
      (node (ref "C85") (pin "2") (pinfunction "2_2") (pintype "passive"))
      (node (ref "C86") (pin "2") (pinfunction "2_2") (pintype "passive"))
      (node (ref "C87") (pin "2") (pinfunction "NEG_2") (pintype "passive"))
      (node (ref "C88") (pin "2") (pinfunction "NEG_2") (pintype "passive"))
      (node (ref "C89") (pin "2") (pinfunction "NEG_2") (pintype "passive"))
      (node (ref "C90") (pin "2") (pinfunction "NEG_2") (pintype "passive"))
      (node (ref "C91") (pin "2") (pinfunction "NEG_2") (pintype "passive"))
      (node (ref "D1") (pin "2") (pinfunction "2_2") (pintype "passive"))
      (node (ref "U3") (pin "2") (pinfunction "VIN_2") (pintype "input"))
      (node (ref "U3") (pin "4") (pinfunction "VIN_(TAB)_4") (pintype "passive"))
    )
  )
)
